# 0x2A.net
KiCad netlist of a schematic drawn in EasyEDA Pro
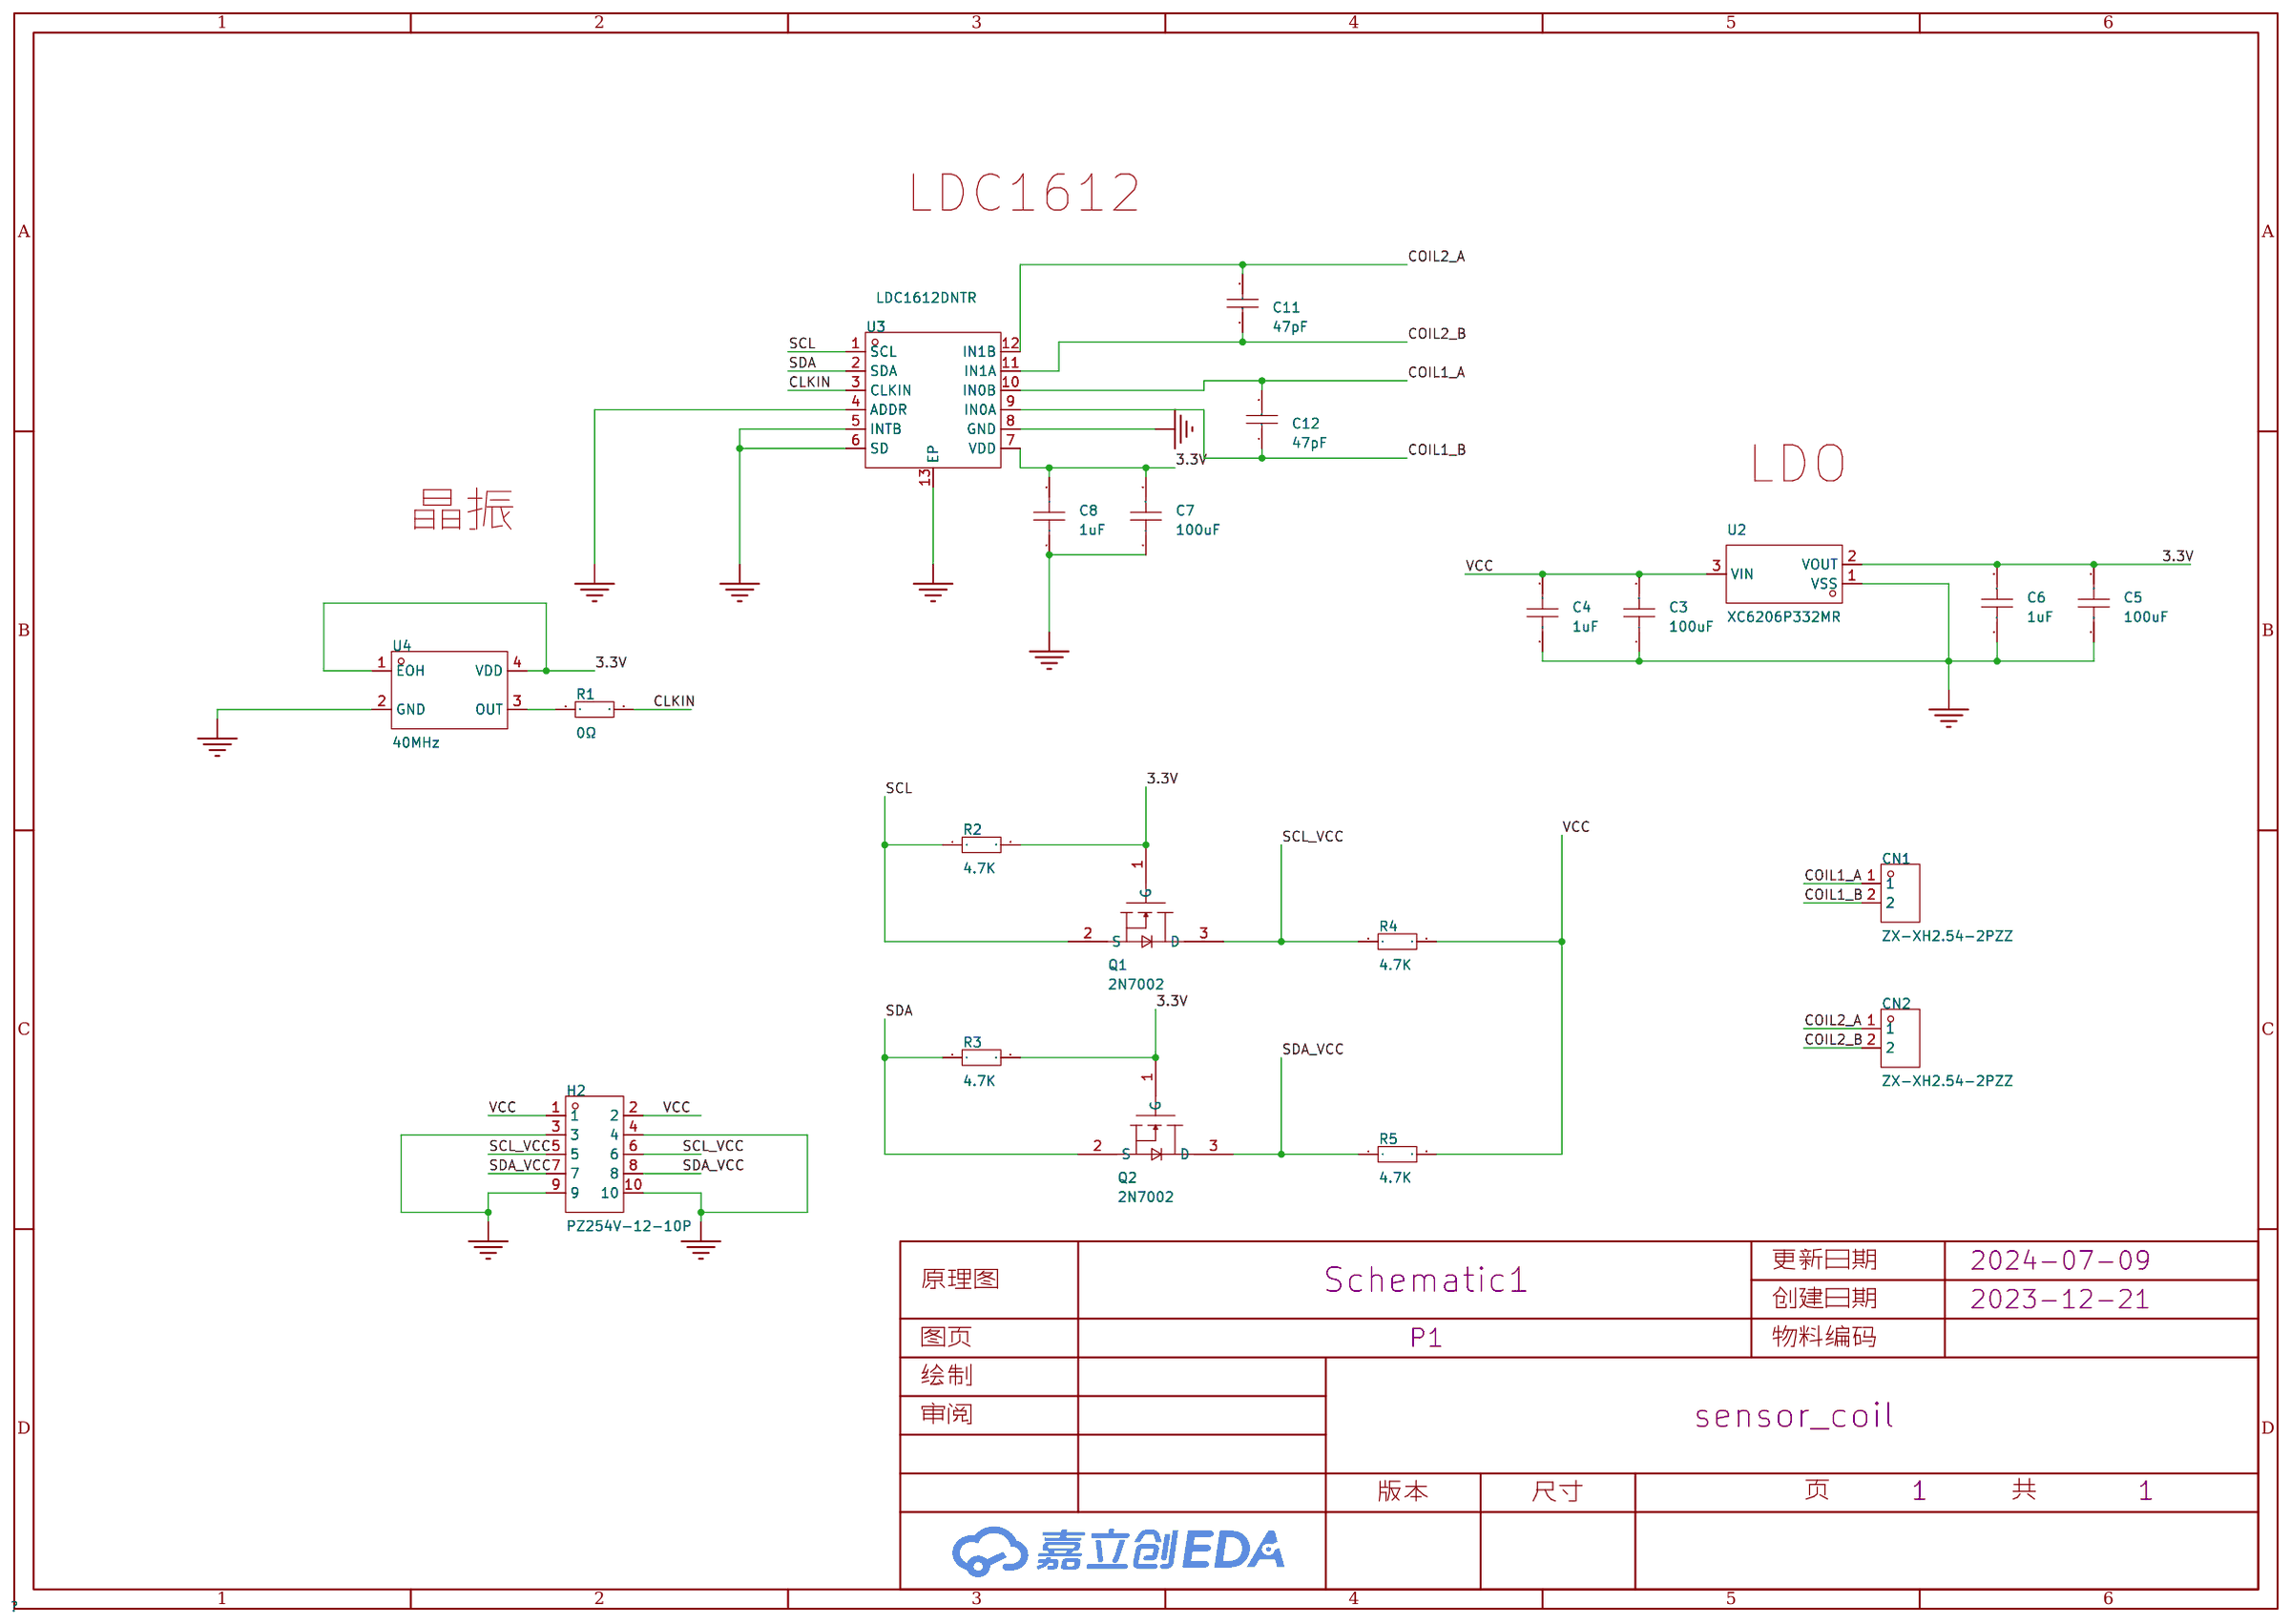
[diagram p0: schematic sheet]

(export (version "E")
  (design (tool "Eeschema 10.0.6"))
  (components
    (comp (ref "C3")
      (value "100uF")
      (footprint "easyedapro:C0603")
      (libsource (lib "easyedapro") (part "CapAcitance"))
    )
    (comp (ref "C4")
      (value "1uF")
      (footprint "easyedapro:C0603")
      (libsource (lib "easyedapro") (part "CapAcitance"))
    )
    (comp (ref "C5")
      (value "100uF")
      (footprint "easyedapro:C0603")
      (libsource (lib "easyedapro") (part "CapAcitance"))
    )
    (comp (ref "C6")
      (value "1uF")
      (footprint "easyedapro:C0603")
      (libsource (lib "easyedapro") (part "CapAcitance"))
    )
    (comp (ref "C7")
      (value "100uF")
      (footprint "easyedapro:C0603")
      (libsource (lib "easyedapro") (part "CapAcitance"))
    )
    (comp (ref "C8")
      (value "1uF")
      (footprint "easyedapro:C0603")
      (libsource (lib "easyedapro") (part "CapAcitance"))
    )
    (comp (ref "C11")
      (value "47pF")
      (footprint "easyedapro:C0402")
      (description "容值:47pF;精度:±5%;额定电压:50V;材质(温度系数):C0G;")
      (fields (field (name "Manufacturer Part") "0402CG470J500NT") (field (name "Manufacturer") "FH(风华)"))
      (libsource (lib "easyedapro") (part "0402CG470J500NT"))
    )
    (comp (ref "C12")
      (value "47pF")
      (footprint "easyedapro:C0402")
      (description "容值:47pF;精度:±5%;额定电压:50V;材质(温度系数):C0G;")
      (fields (field (name "Manufacturer Part") "0402CG470J500NT") (field (name "Manufacturer") "FH(风华)"))
      (libsource (lib "easyedapro") (part "0402CG470J500NT"))
    )
    (comp (ref "CN1")
      (value "ZX-XH2.54-2PZZ")
      (footprint "easyedapro:CONN-TH_2P-P2.50_HX25003-2A")
      (fields (field (name "Manufacturer") "Megastar(兆星)"))
      (libsource (lib "easyedapro") (part "ZX-XH2.54-2PZZ"))
    )
    (comp (ref "CN2")
      (value "ZX-XH2.54-2PZZ")
      (footprint "easyedapro:CONN-TH_2P-P2.50_HX25003-2A")
      (fields (field (name "Manufacturer") "Megastar(兆星)"))
      (libsource (lib "easyedapro") (part "ZX-XH2.54-2PZZ"))
    )
    (comp (ref "H2")
      (value "PZ254V-12-10P")
      (footprint "easyedapro:HDR-TH_10P-P2.54-V-M-R2-C5-S2.54")
      (fields (field (name "Manufacturer") "XFCN(兴飞)"))
      (libsource (lib "easyedapro") (part "PZ254V-12-10P"))
    )
    (comp (ref "Q1")
      (value "2N7002")
      (footprint "easyedapro:SOT-23-3_L2.9-W1.3-P1.90-LS2.4-BR")
      (fields (field (name "Manufacturer") "JSMSEMI(杰盛微)"))
      (libsource (lib "easyedapro") (part "2N7002_C916396"))
    )
    (comp (ref "Q2")
      (value "2N7002")
      (footprint "easyedapro:SOT-23-3_L2.9-W1.3-P1.90-LS2.4-BR")
      (fields (field (name "Manufacturer") "JSMSEMI(杰盛微)"))
      (libsource (lib "easyedapro") (part "2N7002_C916396"))
    )
    (comp (ref "R1") (value "0Ω") (footprint "easyedapro:R0603") (libsource (lib "easyedapro") (part "电阻")))
    (comp (ref "R2") (value "4.7K") (footprint "easyedapro:R0603") (libsource (lib "easyedapro") (part "电阻")))
    (comp (ref "R3") (value "4.7K") (footprint "easyedapro:R0603") (libsource (lib "easyedapro") (part "电阻")))
    (comp (ref "R4") (value "4.7K") (footprint "easyedapro:R0603") (libsource (lib "easyedapro") (part "电阻")))
    (comp (ref "R5") (value "4.7K") (footprint "easyedapro:R0603") (libsource (lib "easyedapro") (part "电阻")))
    (comp (ref "U2")
      (value "XC6206P332MR")
      (footprint "easyedapro:SOT-23-3_L3.0-W1.7-P0.95-LS2.9-BR")
      (description "输出类型:固定;最大输入电压:8V;输出电压:3.3V;最大输出电流:250mA;电源纹波抑制比(PSRR):40dB@(1kHz);输出极性:正极;")
      (fields (field (name "Manufacturer") "UMW(友台半导体)"))
      (libsource (lib "easyedapro") (part "XC6206P332MR_C347376"))
    )
    (comp (ref "U3")
      (value "LDC1612DNTR")
      (footprint "easyedapro:WSON-12_L4.0-W4.0-P0.50-BL-EP")
      (description "LDC1612 2 通道、28 位、高分辨率电感数字转换器")
      (fields (field (name "Manufacturer") "TI(德州仪器)"))
      (libsource (lib "easyedapro") (part "LDC1612DNTR"))
    )
    (comp (ref "U4")
      (value "40MHz")
      (footprint "easyedapro:OSC-SMD_4P-L2.5-W2.0-BL")
      (description "频率:40MHz;输出模式:CMOS;工作电压:3.3V;供电电流:15mA;频率稳定度(全温):±50ppm;")
      (fields (field (name "Manufacturer Part") "625L3C040M00000") (field (name "Manufacturer") "CTS(西迪斯)"))
      (libsource (lib "easyedapro") (part "625L3C040M00000"))
    )
  )
  (nets
    (net (code "1") (name "/3.3V") (class "Default")
      (node (ref "C5") (pin "2") (pinfunction "2_2") (pintype "input"))
      (node (ref "C6") (pin "2") (pinfunction "2_2") (pintype "input"))
      (node (ref "C7") (pin "2") (pinfunction "2_2") (pintype "input"))
      (node (ref "C8") (pin "2") (pinfunction "2_2") (pintype "input"))
      (node (ref "Q1") (pin "1") (pinfunction "G_1") (pintype "unspecified"))
      (node (ref "Q2") (pin "1") (pinfunction "G_1") (pintype "unspecified"))
      (node (ref "R2") (pin "2") (pinfunction "2_2") (pintype "input"))
      (node (ref "R3") (pin "2") (pinfunction "2_2") (pintype "input"))
      (node (ref "U2") (pin "2") (pinfunction "VOUT_2") (pintype "unspecified"))
      (node (ref "U3") (pin "7") (pinfunction "VDD_7") (pintype "unspecified"))
      (node (ref "U4") (pin "1") (pinfunction "EOH_1") (pintype "unspecified"))
      (node (ref "U4") (pin "4") (pinfunction "VDD_4") (pintype "unspecified"))
    )
    (net (code "2") (name "/CLKIN") (class "Default")
      (node (ref "R1") (pin "2") (pinfunction "2_2") (pintype "input"))
      (node (ref "U3") (pin "3") (pinfunction "CLKIN_3") (pintype "unspecified"))
    )
    (net (code "3") (name "/COIL1_A") (class "Default")
      (node (ref "C12") (pin "2") (pinfunction "2_2") (pintype "input"))
      (node (ref "CN1") (pin "1") (pinfunction "1_1") (pintype "unspecified"))
      (node (ref "U3") (pin "10") (pinfunction "IN0B_10") (pintype "unspecified"))
    )
    (net (code "4") (name "/COIL1_B") (class "Default")
      (node (ref "C12") (pin "1") (pinfunction "1_1") (pintype "input"))
      (node (ref "CN1") (pin "2") (pinfunction "2_2") (pintype "unspecified"))
      (node (ref "U3") (pin "9") (pinfunction "IN0A_9") (pintype "unspecified"))
    )
    (net (code "5") (name "/COIL2_A") (class "Default")
      (node (ref "C11") (pin "2") (pinfunction "2_2") (pintype "input"))
      (node (ref "CN2") (pin "1") (pinfunction "1_1") (pintype "unspecified"))
      (node (ref "U3") (pin "12") (pinfunction "IN1B_12") (pintype "unspecified"))
    )
    (net (code "6") (name "/COIL2_B") (class "Default")
      (node (ref "C11") (pin "1") (pinfunction "1_1") (pintype "input"))
      (node (ref "CN2") (pin "2") (pinfunction "2_2") (pintype "unspecified"))
      (node (ref "U3") (pin "11") (pinfunction "IN1A_11") (pintype "unspecified"))
    )
    (net (code "7") (name "/SCL") (class "Default")
      (node (ref "Q1") (pin "2") (pinfunction "S_2") (pintype "unspecified"))
      (node (ref "R2") (pin "1") (pinfunction "1_1") (pintype "input"))
      (node (ref "U3") (pin "1") (pinfunction "SCL_1") (pintype "unspecified"))
    )
    (net (code "8") (name "/SCL_VCC") (class "Default")
      (node (ref "H2") (pin "5") (pinfunction "5_5") (pintype "unspecified"))
      (node (ref "H2") (pin "6") (pinfunction "6_6") (pintype "unspecified"))
      (node (ref "Q1") (pin "3") (pinfunction "D_3") (pintype "unspecified"))
      (node (ref "R4") (pin "1") (pinfunction "1_1") (pintype "input"))
    )
    (net (code "9") (name "/SDA") (class "Default")
      (node (ref "Q2") (pin "2") (pinfunction "S_2") (pintype "unspecified"))
      (node (ref "R3") (pin "1") (pinfunction "1_1") (pintype "input"))
      (node (ref "U3") (pin "2") (pinfunction "SDA_2") (pintype "unspecified"))
    )
    (net (code "10") (name "/SDA_VCC") (class "Default")
      (node (ref "H2") (pin "7") (pinfunction "7_7") (pintype "unspecified"))
      (node (ref "H2") (pin "8") (pinfunction "8_8") (pintype "unspecified"))
      (node (ref "Q2") (pin "3") (pinfunction "D_3") (pintype "unspecified"))
      (node (ref "R5") (pin "1") (pinfunction "1_1") (pintype "input"))
    )
    (net (code "11") (name "/VCC") (class "Default")
      (node (ref "C3") (pin "2") (pinfunction "2_2") (pintype "input"))
      (node (ref "C4") (pin "2") (pinfunction "2_2") (pintype "input"))
      (node (ref "H2") (pin "1") (pinfunction "1_1") (pintype "unspecified"))
      (node (ref "H2") (pin "2") (pinfunction "2_2") (pintype "unspecified"))
      (node (ref "R4") (pin "2") (pinfunction "2_2") (pintype "input"))
      (node (ref "R5") (pin "2") (pinfunction "2_2") (pintype "input"))
      (node (ref "U2") (pin "3") (pinfunction "VIN_3") (pintype "unspecified"))
    )
    (net (code "12") (name "GND") (class "Default")
      (node (ref "C3") (pin "1") (pinfunction "1_1") (pintype "input"))
      (node (ref "C4") (pin "1") (pinfunction "1_1") (pintype "input"))
      (node (ref "C5") (pin "1") (pinfunction "1_1") (pintype "input"))
      (node (ref "C6") (pin "1") (pinfunction "1_1") (pintype "input"))
      (node (ref "C7") (pin "1") (pinfunction "1_1") (pintype "input"))
      (node (ref "C8") (pin "1") (pinfunction "1_1") (pintype "input"))
      (node (ref "H2") (pin "10") (pinfunction "10_10") (pintype "unspecified"))
      (node (ref "H2") (pin "3") (pinfunction "3_3") (pintype "unspecified"))
      (node (ref "H2") (pin "4") (pinfunction "4_4") (pintype "unspecified"))
      (node (ref "H2") (pin "9") (pinfunction "9_9") (pintype "unspecified"))
      (node (ref "U2") (pin "1") (pinfunction "VSS_1") (pintype "unspecified"))
      (node (ref "U3") (pin "13") (pinfunction "EP_13") (pintype "unspecified"))
      (node (ref "U3") (pin "4") (pinfunction "ADDR_4") (pintype "unspecified"))
      (node (ref "U3") (pin "5") (pinfunction "INTB_5") (pintype "unspecified"))
      (node (ref "U3") (pin "6") (pinfunction "SD_6") (pintype "unspecified"))
      (node (ref "U3") (pin "8") (pinfunction "GND_8") (pintype "unspecified"))
      (node (ref "U4") (pin "2") (pinfunction "GND_2") (pintype "unspecified"))
    )
    (net (code "13") (name "Net-(U4-OUT)") (class "Default")
      (node (ref "R1") (pin "1") (pinfunction "1_1") (pintype "input"))
      (node (ref "U4") (pin "3") (pinfunction "OUT_3") (pintype "unspecified"))
    )
  )
)
